# schema-projet-elec.net
KiCad netlist of a schematic drawn in EAGLE
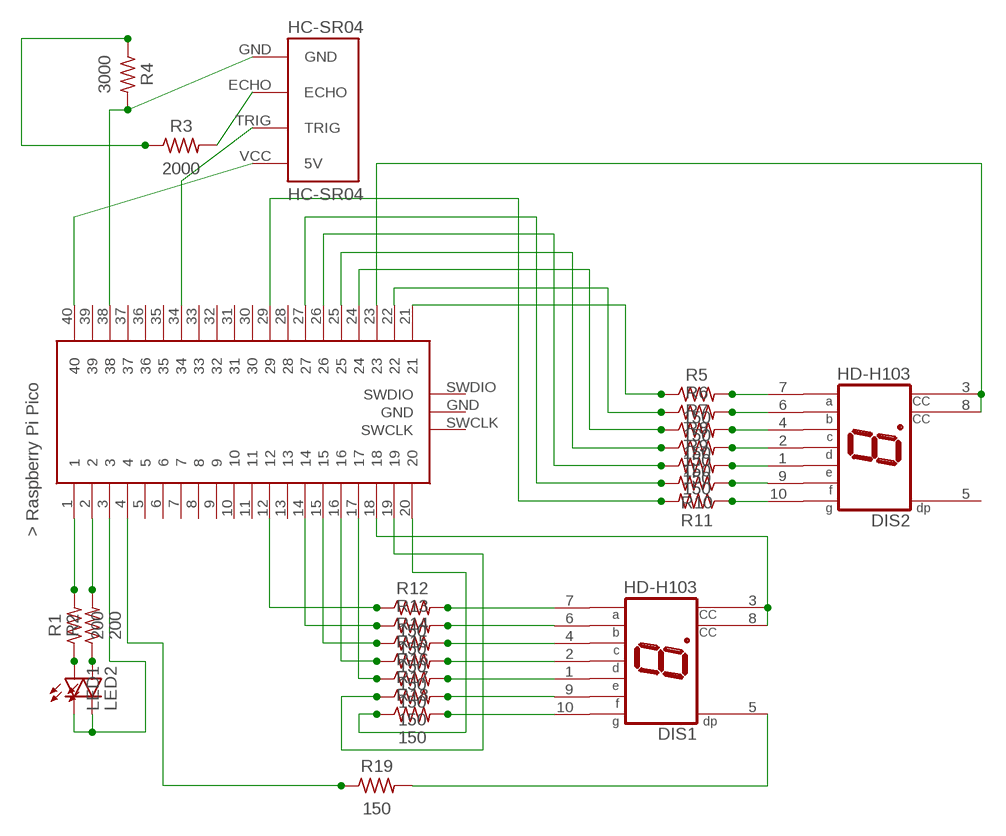
[diagram p0: schematic, sheet 1]

(export (version "E")
  (design (tool "Eeschema 10.0.6"))
  (components
    (comp (ref "DIS1")
      (value "HD-H103")
      (footprint "eagle-import:HDSP-M")
      (libsource (lib "eagle-import") (part "HD-H103"))
    )
    (comp (ref "DIS2")
      (value "HD-H103")
      (footprint "eagle-import:HDSP-M")
      (libsource (lib "eagle-import") (part "HD-H103"))
    )
    (comp (ref "HC-SR04")
      (value "HC-SR04")
      (footprint "eagle-import:HC-SR04_FOOTPRINT")
      (libsource (lib "eagle-import") (part "HC-SR04"))
    )
    (comp (ref "LED1")
      (value "LED5MM")
      (footprint "eagle-import:LED5MM")
      (libsource (lib "eagle-import") (part "LED5MM"))
    )
    (comp (ref "LED2")
      (value "LED5MM")
      (footprint "eagle-import:LED5MM")
      (libsource (lib "eagle-import") (part "LED5MM"))
    )
    (comp (ref "R1")
      (value "200")
      (footprint "eagle-import:RESAD724W46L381D178B")
      (libsource (lib "eagle-import") (part "R-USAXIAL-7.2MM-PITCH_"))
    )
    (comp (ref "R2")
      (value "200")
      (footprint "eagle-import:RESAD724W46L381D178B")
      (libsource (lib "eagle-import") (part "R-USAXIAL-7.2MM-PITCH_"))
    )
    (comp (ref "R3")
      (value "2000")
      (footprint "eagle-import:RESAD724W46L381D178B")
      (libsource (lib "eagle-import") (part "R-USAXIAL-7.2MM-PITCH_"))
    )
    (comp (ref "R4")
      (value "3000")
      (footprint "eagle-import:RESAD724W46L381D178B")
      (libsource (lib "eagle-import") (part "R-USAXIAL-7.2MM-PITCH_"))
    )
    (comp (ref "R5")
      (value "150")
      (footprint "eagle-import:RESAD724W46L381D178B")
      (libsource (lib "eagle-import") (part "R-USAXIAL-7.2MM-PITCH_"))
    )
    (comp (ref "R6")
      (value "150")
      (footprint "eagle-import:RESAD724W46L381D178B")
      (libsource (lib "eagle-import") (part "R-USAXIAL-7.2MM-PITCH_"))
    )
    (comp (ref "R7")
      (value "150")
      (footprint "eagle-import:RESAD724W46L381D178B")
      (libsource (lib "eagle-import") (part "R-USAXIAL-7.2MM-PITCH_"))
    )
    (comp (ref "R8")
      (value "150")
      (footprint "eagle-import:RESAD724W46L381D178B")
      (libsource (lib "eagle-import") (part "R-USAXIAL-7.2MM-PITCH_"))
    )
    (comp (ref "R9")
      (value "150")
      (footprint "eagle-import:RESAD724W46L381D178B")
      (libsource (lib "eagle-import") (part "R-USAXIAL-7.2MM-PITCH_"))
    )
    (comp (ref "R10")
      (value "150")
      (footprint "eagle-import:RESAD724W46L381D178B")
      (libsource (lib "eagle-import") (part "R-USAXIAL-7.2MM-PITCH_"))
    )
    (comp (ref "R11")
      (value "150")
      (footprint "eagle-import:RESAD724W46L381D178B")
      (libsource (lib "eagle-import") (part "R-USAXIAL-7.2MM-PITCH_"))
    )
    (comp (ref "R12")
      (value "150")
      (footprint "eagle-import:RESAD724W46L381D178B")
      (libsource (lib "eagle-import") (part "R-USAXIAL-7.2MM-PITCH_"))
    )
    (comp (ref "R13")
      (value "150")
      (footprint "eagle-import:RESAD724W46L381D178B")
      (libsource (lib "eagle-import") (part "R-USAXIAL-7.2MM-PITCH_"))
    )
    (comp (ref "R14")
      (value "150")
      (footprint "eagle-import:RESAD724W46L381D178B")
      (libsource (lib "eagle-import") (part "R-USAXIAL-7.2MM-PITCH_"))
    )
    (comp (ref "R15")
      (value "150")
      (footprint "eagle-import:RESAD724W46L381D178B")
      (libsource (lib "eagle-import") (part "R-USAXIAL-7.2MM-PITCH_"))
    )
    (comp (ref "R16")
      (value "150")
      (footprint "eagle-import:RESAD724W46L381D178B")
      (libsource (lib "eagle-import") (part "R-USAXIAL-7.2MM-PITCH_"))
    )
    (comp (ref "R17")
      (value "150")
      (footprint "eagle-import:RESAD724W46L381D178B")
      (libsource (lib "eagle-import") (part "R-USAXIAL-7.2MM-PITCH_"))
    )
    (comp (ref "R18")
      (value "150")
      (footprint "eagle-import:RESAD724W46L381D178B")
      (libsource (lib "eagle-import") (part "R-USAXIAL-7.2MM-PITCH_"))
    )
    (comp (ref "R19")
      (value "150")
      (footprint "eagle-import:RESAD724W46L381D178B")
      (libsource (lib "eagle-import") (part "R-USAXIAL-7.2MM-PITCH_"))
    )
    (comp (ref "U$1")
      (value "RASPBERRY-PI-PICO_TH")
      (footprint "eagle-import:FT_RASPBERRY-PI-PICO_TH")
      (libsource (lib "eagle-import") (part "RASPBERRY-PI-PICO_TH"))
    )
  )
  (nets
    (net (code "1") (name "Net-(DIS1-A)") (class "Default")
      (node (ref "DIS1") (pin "7") (pinfunction "A_7") (pintype "passive"))
      (node (ref "R12") (pin "2") (pinfunction "2_2") (pintype "passive"))
    )
    (net (code "2") (name "Net-(DIS1-B)") (class "Default")
      (node (ref "DIS1") (pin "6") (pinfunction "B_6") (pintype "passive"))
      (node (ref "R13") (pin "2") (pinfunction "2_2") (pintype "passive"))
    )
    (net (code "3") (name "Net-(DIS1-C)") (class "Default")
      (node (ref "DIS1") (pin "4") (pinfunction "C_4") (pintype "passive"))
      (node (ref "R14") (pin "2") (pinfunction "2_2") (pintype "passive"))
    )
    (net (code "4") (name "Net-(DIS1-CC-Pad3)") (class "Default")
      (node (ref "DIS1") (pin "3") (pinfunction "CC_3") (pintype "passive"))
      (node (ref "DIS1") (pin "8") (pinfunction "CC_8") (pintype "passive"))
      (node (ref "U$1") (pin "18") (pinfunction "18_18") (pintype "bidirectional"))
    )
    (net (code "5") (name "Net-(DIS1-D)") (class "Default")
      (node (ref "DIS1") (pin "2") (pinfunction "D_2") (pintype "passive"))
      (node (ref "R15") (pin "2") (pinfunction "2_2") (pintype "passive"))
    )
    (net (code "6") (name "Net-(DIS1-DP)") (class "Default")
      (node (ref "DIS1") (pin "5") (pinfunction "DP_5") (pintype "passive"))
      (node (ref "R19") (pin "2") (pinfunction "2_2") (pintype "passive"))
    )
    (net (code "7") (name "Net-(DIS1-E)") (class "Default")
      (node (ref "DIS1") (pin "1") (pinfunction "E_1") (pintype "passive"))
      (node (ref "R16") (pin "2") (pinfunction "2_2") (pintype "passive"))
    )
    (net (code "8") (name "Net-(DIS1-F)") (class "Default")
      (node (ref "DIS1") (pin "9") (pinfunction "F_9") (pintype "passive"))
      (node (ref "R17") (pin "2") (pinfunction "2_2") (pintype "passive"))
    )
    (net (code "9") (name "Net-(DIS1-G)") (class "Default")
      (node (ref "DIS1") (pin "10") (pinfunction "G_10") (pintype "passive"))
      (node (ref "R18") (pin "2") (pinfunction "2_2") (pintype "passive"))
    )
    (net (code "10") (name "Net-(DIS2-A)") (class "Default")
      (node (ref "DIS2") (pin "7") (pinfunction "A_7") (pintype "passive"))
      (node (ref "R5") (pin "2") (pinfunction "2_2") (pintype "passive"))
    )
    (net (code "11") (name "Net-(DIS2-B)") (class "Default")
      (node (ref "DIS2") (pin "6") (pinfunction "B_6") (pintype "passive"))
      (node (ref "R6") (pin "2") (pinfunction "2_2") (pintype "passive"))
    )
    (net (code "12") (name "Net-(DIS2-C)") (class "Default")
      (node (ref "DIS2") (pin "4") (pinfunction "C_4") (pintype "passive"))
      (node (ref "R7") (pin "2") (pinfunction "2_2") (pintype "passive"))
    )
    (net (code "13") (name "Net-(DIS2-CC-Pad3)") (class "Default")
      (node (ref "DIS2") (pin "3") (pinfunction "CC_3") (pintype "passive"))
      (node (ref "DIS2") (pin "8") (pinfunction "CC_8") (pintype "passive"))
      (node (ref "U$1") (pin "23") (pinfunction "23_23") (pintype "bidirectional"))
    )
    (net (code "14") (name "Net-(DIS2-D)") (class "Default")
      (node (ref "DIS2") (pin "2") (pinfunction "D_2") (pintype "passive"))
      (node (ref "R8") (pin "2") (pinfunction "2_2") (pintype "passive"))
    )
    (net (code "15") (name "Net-(DIS2-E)") (class "Default")
      (node (ref "DIS2") (pin "1") (pinfunction "E_1") (pintype "passive"))
      (node (ref "R9") (pin "2") (pinfunction "2_2") (pintype "passive"))
    )
    (net (code "16") (name "Net-(DIS2-F)") (class "Default")
      (node (ref "DIS2") (pin "9") (pinfunction "F_9") (pintype "passive"))
      (node (ref "R10") (pin "1") (pinfunction "1_1") (pintype "passive"))
    )
    (net (code "17") (name "Net-(DIS2-G)") (class "Default")
      (node (ref "DIS2") (pin "10") (pinfunction "G_10") (pintype "passive"))
      (node (ref "R11") (pin "1") (pinfunction "1_1") (pintype "passive"))
    )
    (net (code "18") (name "Net-(HC-SR04-5V)") (class "Default")
      (node (ref "HC-SR04") (pin "VCC") (pinfunction "5V_VCC") (pintype "bidirectional"))
      (node (ref "U$1") (pin "40") (pinfunction "40_40") (pintype "bidirectional"))
    )
    (net (code "19") (name "Net-(HC-SR04-PadECHO)") (class "Default")
      (node (ref "HC-SR04") (pin "ECHO") (pinfunction "ECHO_ECHO") (pintype "bidirectional"))
      (node (ref "R3") (pin "2") (pinfunction "2_2") (pintype "passive"))
    )
    (net (code "20") (name "Net-(HC-SR04-PadGND)") (class "Default")
      (node (ref "HC-SR04") (pin "GND") (pinfunction "GND_GND") (pintype "bidirectional"))
      (node (ref "R4") (pin "2") (pinfunction "2_2") (pintype "passive"))
      (node (ref "U$1") (pin "38") (pinfunction "38_38") (pintype "bidirectional"))
    )
    (net (code "21") (name "Net-(HC-SR04-PadTRIG)") (class "Default")
      (node (ref "HC-SR04") (pin "TRIG") (pinfunction "TRIG_TRIG") (pintype "bidirectional"))
      (node (ref "U$1") (pin "34") (pinfunction "34_34") (pintype "bidirectional"))
    )
    (net (code "22") (name "Net-(LED1-C)") (class "Default")
      (node (ref "LED1") (pin "K") (pinfunction "C_K") (pintype "passive"))
      (node (ref "LED2") (pin "K") (pinfunction "C_K") (pintype "passive"))
      (node (ref "U$1") (pin "3") (pinfunction "3_3") (pintype "bidirectional"))
    )
    (net (code "23") (name "Net-(LED1-PadA)") (class "Default")
      (node (ref "LED1") (pin "A") (pinfunction "A_A") (pintype "passive"))
      (node (ref "R1") (pin "1") (pinfunction "1_1") (pintype "passive"))
    )
    (net (code "24") (name "Net-(LED2-PadA)") (class "Default")
      (node (ref "LED2") (pin "A") (pinfunction "A_A") (pintype "passive"))
      (node (ref "R2") (pin "1") (pinfunction "1_1") (pintype "passive"))
    )
    (net (code "25") (name "Net-(R1-Pad2)") (class "Default")
      (node (ref "R1") (pin "2") (pinfunction "2_2") (pintype "passive"))
      (node (ref "U$1") (pin "1") (pinfunction "1_1") (pintype "bidirectional"))
    )
    (net (code "26") (name "Net-(R2-Pad2)") (class "Default")
      (node (ref "R2") (pin "2") (pinfunction "2_2") (pintype "passive"))
      (node (ref "U$1") (pin "2") (pinfunction "2_2") (pintype "bidirectional"))
    )
    (net (code "27") (name "Net-(R3-Pad1)") (class "Default")
      (node (ref "R3") (pin "1") (pinfunction "1_1") (pintype "passive"))
      (node (ref "R4") (pin "1") (pinfunction "1_1") (pintype "passive"))
    )
    (net (code "28") (name "Net-(R5-Pad1)") (class "Default")
      (node (ref "R5") (pin "1") (pinfunction "1_1") (pintype "passive"))
      (node (ref "U$1") (pin "21") (pinfunction "21_21") (pintype "bidirectional"))
    )
    (net (code "29") (name "Net-(R6-Pad1)") (class "Default")
      (node (ref "R6") (pin "1") (pinfunction "1_1") (pintype "passive"))
      (node (ref "U$1") (pin "22") (pinfunction "22_22") (pintype "bidirectional"))
    )
    (net (code "30") (name "Net-(R7-Pad1)") (class "Default")
      (node (ref "R7") (pin "1") (pinfunction "1_1") (pintype "passive"))
      (node (ref "U$1") (pin "24") (pinfunction "24_24") (pintype "bidirectional"))
    )
    (net (code "31") (name "Net-(R8-Pad1)") (class "Default")
      (node (ref "R8") (pin "1") (pinfunction "1_1") (pintype "passive"))
      (node (ref "U$1") (pin "25") (pinfunction "25_25") (pintype "bidirectional"))
    )
    (net (code "32") (name "Net-(R9-Pad1)") (class "Default")
      (node (ref "R9") (pin "1") (pinfunction "1_1") (pintype "passive"))
      (node (ref "U$1") (pin "26") (pinfunction "26_26") (pintype "bidirectional"))
    )
    (net (code "33") (name "Net-(R10-Pad2)") (class "Default")
      (node (ref "R10") (pin "2") (pinfunction "2_2") (pintype "passive"))
      (node (ref "U$1") (pin "27") (pinfunction "27_27") (pintype "bidirectional"))
    )
    (net (code "34") (name "Net-(R11-Pad2)") (class "Default")
      (node (ref "R11") (pin "2") (pinfunction "2_2") (pintype "passive"))
      (node (ref "U$1") (pin "29") (pinfunction "29_29") (pintype "bidirectional"))
    )
    (net (code "35") (name "Net-(R12-Pad1)") (class "Default")
      (node (ref "R12") (pin "1") (pinfunction "1_1") (pintype "passive"))
      (node (ref "U$1") (pin "12") (pinfunction "12_12") (pintype "bidirectional"))
    )
    (net (code "36") (name "Net-(R13-Pad1)") (class "Default")
      (node (ref "R13") (pin "1") (pinfunction "1_1") (pintype "passive"))
      (node (ref "U$1") (pin "14") (pinfunction "14_14") (pintype "bidirectional"))
    )
    (net (code "37") (name "Net-(R14-Pad1)") (class "Default")
      (node (ref "R14") (pin "1") (pinfunction "1_1") (pintype "passive"))
      (node (ref "U$1") (pin "15") (pinfunction "15_15") (pintype "bidirectional"))
    )
    (net (code "38") (name "Net-(R15-Pad1)") (class "Default")
      (node (ref "R15") (pin "1") (pinfunction "1_1") (pintype "passive"))
      (node (ref "U$1") (pin "16") (pinfunction "16_16") (pintype "bidirectional"))
    )
    (net (code "39") (name "Net-(R16-Pad1)") (class "Default")
      (node (ref "R16") (pin "1") (pinfunction "1_1") (pintype "passive"))
      (node (ref "U$1") (pin "17") (pinfunction "17_17") (pintype "bidirectional"))
    )
    (net (code "40") (name "Net-(R17-Pad1)") (class "Default")
      (node (ref "R17") (pin "1") (pinfunction "1_1") (pintype "passive"))
      (node (ref "U$1") (pin "19") (pinfunction "19_19") (pintype "bidirectional"))
    )
    (net (code "41") (name "Net-(R18-Pad1)") (class "Default")
      (node (ref "R18") (pin "1") (pinfunction "1_1") (pintype "passive"))
      (node (ref "U$1") (pin "20") (pinfunction "20_20") (pintype "bidirectional"))
    )
    (net (code "42") (name "Net-(R19-Pad1)") (class "Default")
      (node (ref "R19") (pin "1") (pinfunction "1_1") (pintype "passive"))
      (node (ref "U$1") (pin "4") (pinfunction "4_4") (pintype "bidirectional"))
    )
    (net (code "43") (name "unconnected-(DIS2-DP-Pad5)") (class "Default")
      (node (ref "DIS2") (pin "5") (pinfunction "DP_5") (pintype "passive"))
    )
    (net (code "44") (name "unconnected-(U$1-Pad5)") (class "Default")
      (node (ref "U$1") (pin "5") (pinfunction "5_5") (pintype "bidirectional"))
    )
    (net (code "45") (name "unconnected-(U$1-Pad6)") (class "Default")
      (node (ref "U$1") (pin "6") (pinfunction "6_6") (pintype "bidirectional"))
    )
    (net (code "46") (name "unconnected-(U$1-Pad7)") (class "Default")
      (node (ref "U$1") (pin "7") (pinfunction "7_7") (pintype "bidirectional"))
    )
    (net (code "47") (name "unconnected-(U$1-Pad8)") (class "Default")
      (node (ref "U$1") (pin "8") (pinfunction "8_8") (pintype "bidirectional"))
    )
    (net (code "48") (name "unconnected-(U$1-Pad9)") (class "Default")
      (node (ref "U$1") (pin "9") (pinfunction "9_9") (pintype "bidirectional"))
    )
    (net (code "49") (name "unconnected-(U$1-Pad10)") (class "Default")
      (node (ref "U$1") (pin "10") (pinfunction "10_10") (pintype "bidirectional"))
    )
    (net (code "50") (name "unconnected-(U$1-Pad11)") (class "Default")
      (node (ref "U$1") (pin "11") (pinfunction "11_11") (pintype "bidirectional"))
    )
    (net (code "51") (name "unconnected-(U$1-Pad13)") (class "Default")
      (node (ref "U$1") (pin "13") (pinfunction "13_13") (pintype "bidirectional"))
    )
    (net (code "52") (name "unconnected-(U$1-Pad28)") (class "Default")
      (node (ref "U$1") (pin "28") (pinfunction "28_28") (pintype "bidirectional"))
    )
    (net (code "53") (name "unconnected-(U$1-Pad30)") (class "Default")
      (node (ref "U$1") (pin "30") (pinfunction "30_30") (pintype "bidirectional"))
    )
    (net (code "54") (name "unconnected-(U$1-Pad31)") (class "Default")
      (node (ref "U$1") (pin "31") (pinfunction "31_31") (pintype "bidirectional"))
    )
    (net (code "55") (name "unconnected-(U$1-Pad32)") (class "Default")
      (node (ref "U$1") (pin "32") (pinfunction "32_32") (pintype "bidirectional"))
    )
    (net (code "56") (name "unconnected-(U$1-Pad33)") (class "Default")
      (node (ref "U$1") (pin "33") (pinfunction "33_33") (pintype "bidirectional"))
    )
    (net (code "57") (name "unconnected-(U$1-Pad35)") (class "Default")
      (node (ref "U$1") (pin "35") (pinfunction "35_35") (pintype "bidirectional"))
    )
    (net (code "58") (name "unconnected-(U$1-Pad36)") (class "Default")
      (node (ref "U$1") (pin "36") (pinfunction "36_36") (pintype "bidirectional"))
    )
    (net (code "59") (name "unconnected-(U$1-Pad37)") (class "Default")
      (node (ref "U$1") (pin "37") (pinfunction "37_37") (pintype "bidirectional"))
    )
    (net (code "60") (name "unconnected-(U$1-Pad39)") (class "Default")
      (node (ref "U$1") (pin "39") (pinfunction "39_39") (pintype "bidirectional"))
    )
    (net (code "61") (name "unconnected-(U$1-PadGND)") (class "Default")
      (node (ref "U$1") (pin "GND") (pinfunction "GND_GND") (pintype "bidirectional"))
    )
    (net (code "62") (name "unconnected-(U$1-PadSWCLK)") (class "Default")
      (node (ref "U$1") (pin "SWCLK") (pinfunction "SWCLK_SWCLK") (pintype "bidirectional"))
    )
    (net (code "63") (name "unconnected-(U$1-PadSWDIO)") (class "Default")
      (node (ref "U$1") (pin "SWDIO") (pinfunction "SWDIO_SWDIO") (pintype "bidirectional"))
    )
  )
)
